# LevelShifter_Rev02.net
KiCad netlist of a schematic drawn in EAGLE
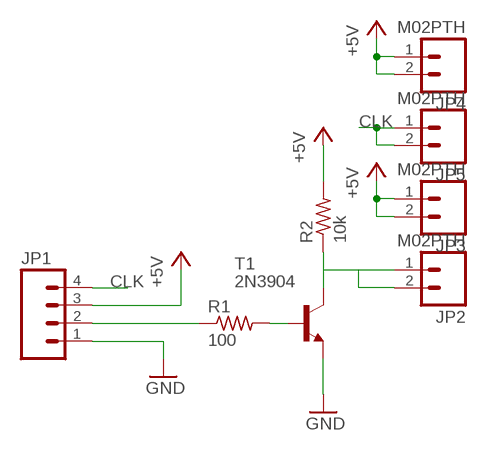
[diagram p0: schematic, sheet 1]

(export (version "E")
  (design (tool "Eeschema 10.0.6"))
  (components
    (comp (ref "JP1")
      (value "M04SCREW")
      (footprint "eagle-import:SCREWTERMINAL-3.5MM-4")
      (libsource (lib "eagle-import") (part "M04SCREW"))
    )
    (comp (ref "JP2")
      (value "M02PTH")
      (footprint "eagle-import:1X02")
      (libsource (lib "eagle-import") (part "M02PTH"))
    )
    (comp (ref "JP3")
      (value "M02PTH")
      (footprint "eagle-import:1X02")
      (libsource (lib "eagle-import") (part "M02PTH"))
    )
    (comp (ref "JP4")
      (value "M02PTH")
      (footprint "eagle-import:1X02")
      (libsource (lib "eagle-import") (part "M02PTH"))
    )
    (comp (ref "JP5")
      (value "M02PTH")
      (footprint "eagle-import:1X02")
      (libsource (lib "eagle-import") (part "M02PTH"))
    )
    (comp (ref "R1")
      (value "100")
      (footprint "eagle-import:0204_7")
      (libsource (lib "eagle-import") (part "R-US_0204/7"))
    )
    (comp (ref "R2")
      (value "10k")
      (footprint "eagle-import:0204_7")
      (libsource (lib "eagle-import") (part "R-US_0204/7"))
    )
    (comp (ref "T1")
      (value "2N3904")
      (footprint "eagle-import:TO92")
      (libsource (lib "eagle-import") (part "2N3904"))
    )
  )
  (nets
    (net (code "1") (name "+5V") (class "Default")
      (node (ref "JP1") (pin "3") (pinfunction "3_3") (pintype "passive"))
      (node (ref "JP3") (pin "1") (pinfunction "1_1") (pintype "passive"))
      (node (ref "JP3") (pin "2") (pinfunction "2_2") (pintype "passive"))
      (node (ref "JP4") (pin "1") (pinfunction "1_1") (pintype "passive"))
      (node (ref "JP4") (pin "2") (pinfunction "2_2") (pintype "passive"))
      (node (ref "R2") (pin "2") (pinfunction "2_2") (pintype "passive"))
    )
    (net (code "2") (name "/CLK") (class "Default")
      (node (ref "JP1") (pin "4") (pinfunction "4_4") (pintype "passive"))
      (node (ref "JP5") (pin "1") (pinfunction "1_1") (pintype "passive"))
      (node (ref "JP5") (pin "2") (pinfunction "2_2") (pintype "passive"))
    )
    (net (code "3") (name "GND") (class "Default")
      (node (ref "JP1") (pin "1") (pinfunction "1_1") (pintype "passive"))
      (node (ref "T1") (pin "3") (pinfunction "E_3") (pintype "passive"))
    )
    (net (code "4") (name "Net-(JP1-Pad2)") (class "Default")
      (node (ref "JP1") (pin "2") (pinfunction "2_2") (pintype "passive"))
      (node (ref "R1") (pin "1") (pinfunction "1_1") (pintype "passive"))
    )
    (net (code "5") (name "Net-(T1-B)") (class "Default")
      (node (ref "R1") (pin "2") (pinfunction "2_2") (pintype "passive"))
      (node (ref "T1") (pin "2") (pinfunction "B_2") (pintype "passive"))
    )
    (net (code "6") (name "Net-(T1-C)") (class "Default")
      (node (ref "JP2") (pin "1") (pinfunction "1_1") (pintype "passive"))
      (node (ref "JP2") (pin "2") (pinfunction "2_2") (pintype "passive"))
      (node (ref "R2") (pin "1") (pinfunction "1_1") (pintype "passive"))
      (node (ref "T1") (pin "1") (pinfunction "C_1") (pintype "passive"))
    )
  )
)
